# Sheet8.net
KiCad netlist of a schematic drawn in Altium Designer
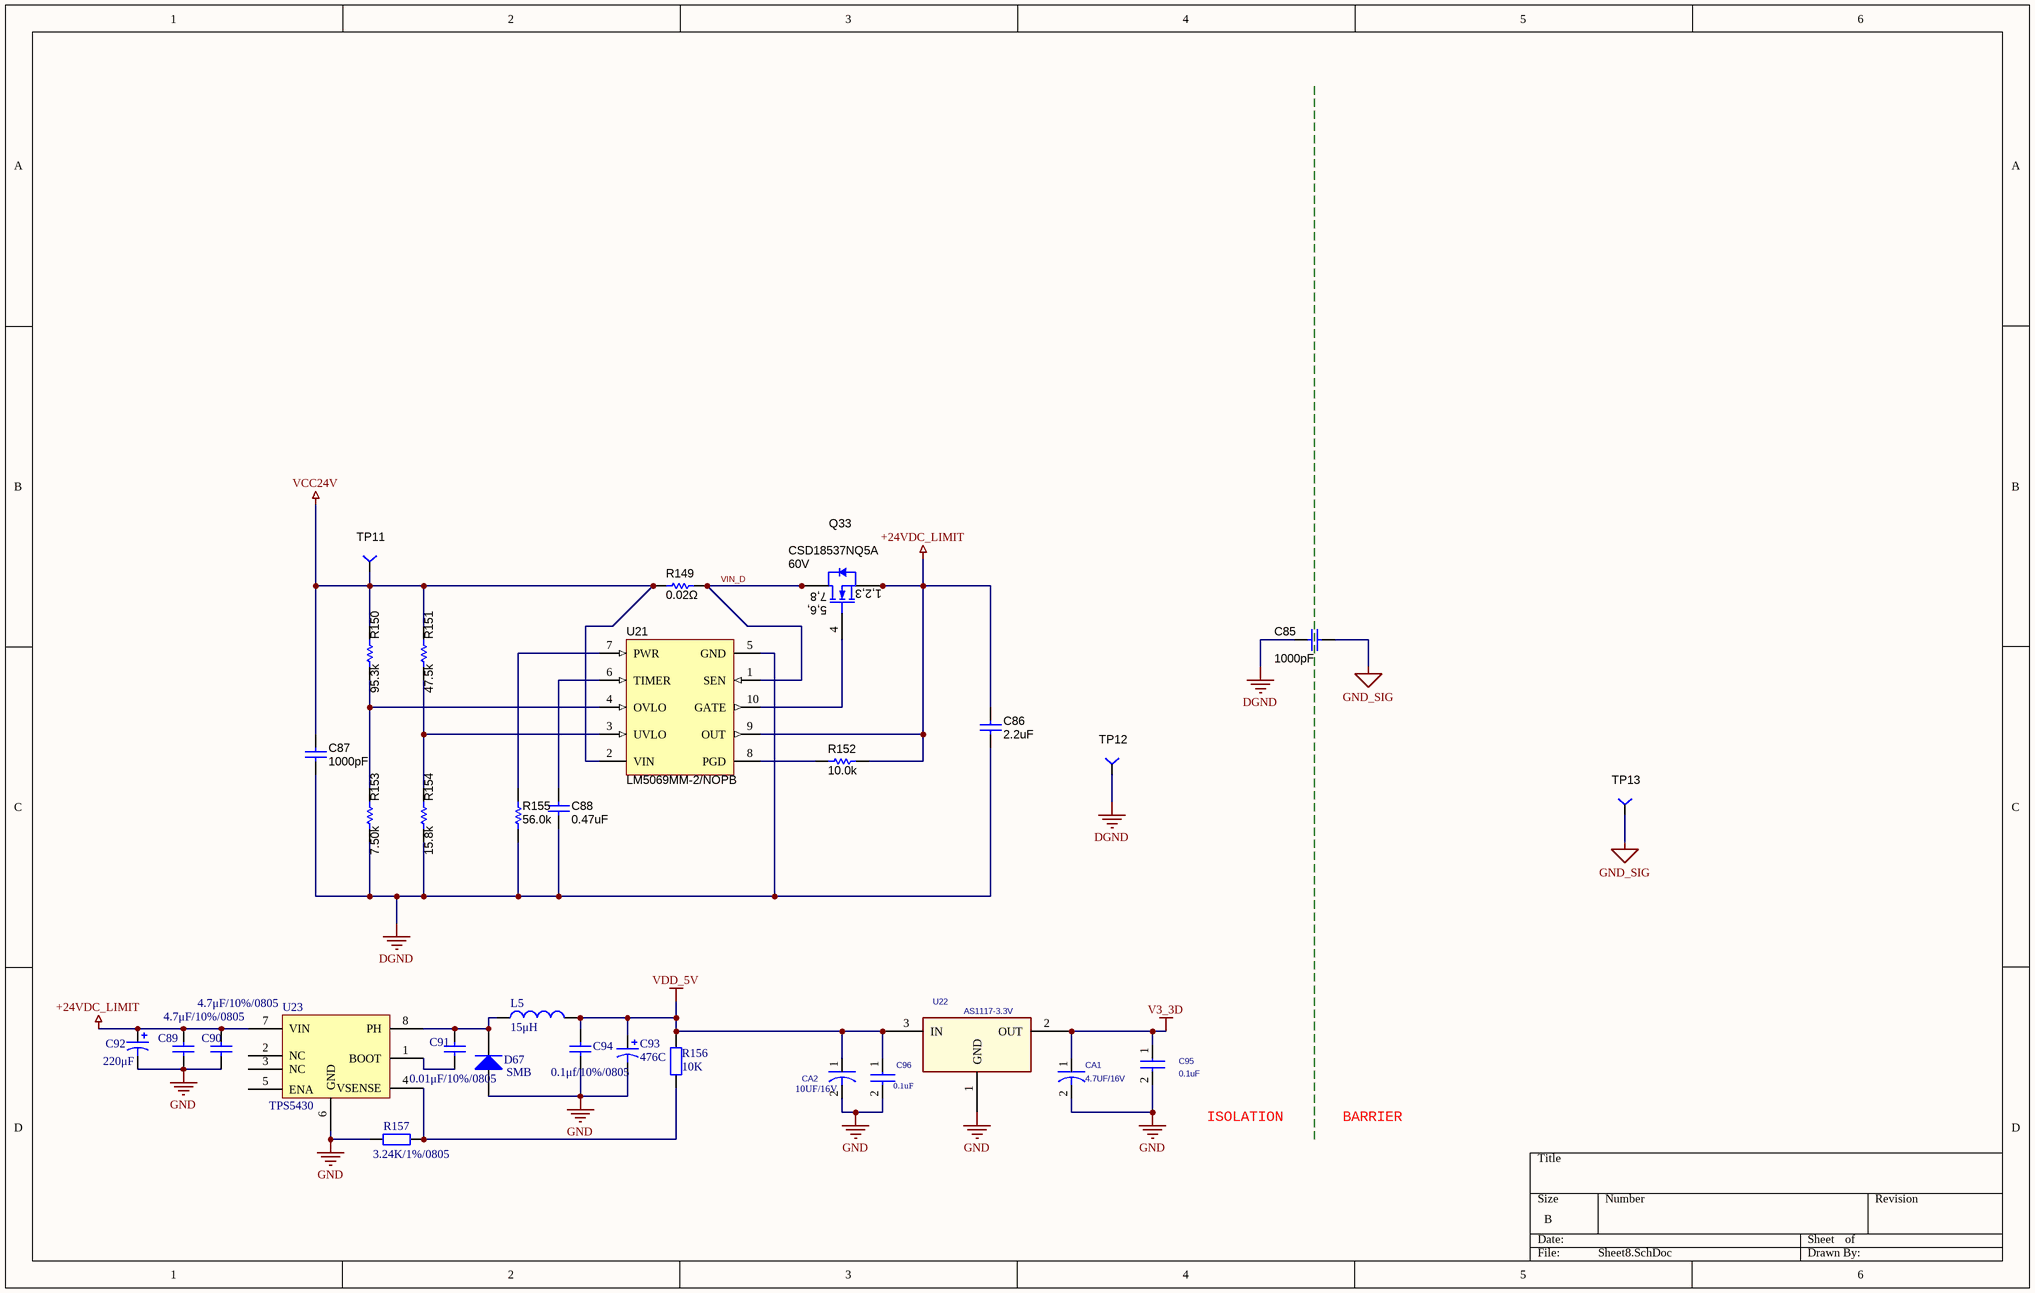
[diagram p0: Sheet8.SchDoc]

(export (version "E")
  (design (tool "Eeschema 10.0.6"))
  (components
    (comp (ref "C85")
      (value "1000pF")
      (footprint "1206")
      (description "CAP, CERM, 1000pF, 2KV 10% X7R 1206")
      (fields
        (field (name "PARTNUMBER") "202R18W102KV4E")
        (field (name "MANUFACTURER") "Johanson Dielectrics Inc")
        (field (name "PUBLISHER") "Texas Instruments")
      )
      (libsource (lib "TI-INDIA-ALTIUM") (part "202R18W102KV4E"))
    )
    (comp (ref "C86")
      (value "GRM32ER72A225KA35L")
      (footprint "1210")
      (description "CAP, CERM, 2.2uF, 100V, +/-10%, X7R, 1210")
      (fields
        (field (name "VALUEDISPLAYED") "2.2uF")
        (field (name "MANUFACTURER") "MuRata")
        (field (name "PUBLISHER") "Texas Instruments")
      )
      (libsource (lib "Capacitor_Ceramic") (part "GRM32ER72A225KA35L"))
    )
    (comp (ref "C87")
      (value "06031C102JAT2A")
      (footprint "0805_cap")
      (description "CAP, CERM, 1000pF, 100V, +/-5%, X7R, 0603")
      (fields
        (field (name "VALUEDISPLAYED") "1000pF")
        (field (name "MANUFACTURER") "AVX")
        (field (name "PUBLISHER") "Texas Instruments")
      )
      (libsource (lib "Capacitor_Ceramic") (part "06031C102JAT2A"))
    )
    (comp (ref "C88")
      (value "UMK107ABJ474KA-T")
      (footprint "0805_cap")
      (description "CAP, CERM, 0.47uF, 50V, 10%, X5R, 0603")
      (fields
        (field (name "MANUFACTURER") "Taiyo Yuden")
        (field (name "VALUEDISPLAYED") "0.47uF")
        (field (name "PUBLISHER") "Texas Instruments")
      )
      (libsource (lib "TI-INDIA-ALTIUM") (part "UMK107ABJ474KA-T"))
    )
    (comp (ref "C89")
      (value "4.7μF/10%/0805")
      (footprint "0805_CAP")
      (description "Capacitor")
      (fields (field (name "PUBLISHER") "Altium Limited"))
      (libsource (lib "Miscellaneous Devices") (part "Cap"))
    )
    (comp (ref "C90")
      (value "4.7μF/10%/0805")
      (footprint "0805_CAP")
      (description "Capacitor")
      (fields (field (name "PUBLISHER") "Altium Limited"))
      (libsource (lib "Miscellaneous Devices") (part "Cap"))
    )
    (comp (ref "C91")
      (value "0.01μF/10%/0805")
      (footprint "0805_CAP")
      (description "Capacitor")
      (fields (field (name "PUBLISHER") "Altium Limited"))
      (libsource (lib "Miscellaneous Devices") (part "Cap"))
    )
    (comp (ref "C92")
      (value "220μF")
      (footprint "CZ3.0/6.5")
      (description "Polarized Capacitor (Radial)")
      (fields (field (name "PUBLISHER") "Altium Limited"))
      (libsource (lib "Miscellaneous Devices") (part "Cap Pol1"))
    )
    (comp (ref "C93")
      (value "476C")
      (footprint "7343-43")
      (description "Polarized Capacitor (Radial)")
      (fields (field (name "PUBLISHER") "Altium Limited"))
      (libsource (lib "Miscellaneous Devices") (part "Cap Pol1"))
    )
    (comp (ref "C94")
      (value "0.1μf/10%/0805")
      (footprint "0805_CAP")
      (description "Capacitor")
      (fields (field (name "PUBLISHER") "Altium Limited"))
      (libsource (lib "Miscellaneous Devices") (part "Cap"))
    )
    (comp (ref "C95") (value "0.1uF") (footprint "0805_CAP") (libsource (lib "v3") (part "C")))
    (comp (ref "C96") (value "0.1uF") (footprint "0805_CAP") (libsource (lib "v3") (part "C")))
    (comp (ref "CA1") (value "4.7UF/16V") (footprint "3528cap") (libsource (lib "v3") (part "ECAP")))
    (comp (ref "CA2") (value "10UF/16V") (footprint "3528cap") (libsource (lib "v3") (part "ECAP")))
    (comp (ref "D67")
      (value "SMB")
      (footprint "SMB")
      (description "3 Amp Medium Power Silicon Rectifier Diode")
      (fields (field (name "PUBLISHER") "Altium Limited"))
      (libsource (lib "Miscellaneous Devices") (part "Diode 1N5408"))
    )
    (comp (ref "L5")
      (value "15μH")
      (footprint "GSDS104C2")
      (description "Inductor")
      (fields (field (name "PUBLISHER") "Altium Limited"))
      (libsource (lib "Miscellaneous Devices") (part "Inductor"))
    )
    (comp (ref "Q33")
      (value "CSD18537NQ5A")
      (footprint "TRANS_NexFET_Q5A")
      (description "MOSFET, N-CH, 60V, 50A, SON 5x6mm")
      (fields
        (field (name "ALTIUM_VALUE") "60V")
        (field (name "MANUFACTURER") "Texas Instruments")
        (field (name "PUBLISHER") "Texas Instruments")
      )
      (libsource (lib "FETs") (part "CSD18537NQ5A"))
    )
    (comp (ref "R149")
      (value "0.02Ω")
      (footprint "1206")
      (description "RES, 0.02 ohm, 1%, 1W, 1206")
      (fields
        (field (name "PARTNUMBER") "PRL1632-R020-F-T1")
        (field (name "MANUFACTURER") "Susumu Co Ltd")
        (field (name "PUBLISHER") "Texas Instruments")
      )
      (libsource (lib "Resistor_1206") (part "PRL1632-R020-F-T1"))
    )
    (comp (ref "R150")
      (value "95.3k")
      (footprint "0805")
      (description "RES, 95.3k ohm, 1%, 0.1W, 0603")
      (fields
        (field (name "PARTNUMBER") "CRCW060395K3FKEA")
        (field (name "MANUFACTURER") "Vishay-Dale")
        (field (name "PUBLISHER") "Texas Instruments")
      )
      (libsource (lib "Resistor_0603") (part "CRCW060395K3FKEA"))
    )
    (comp (ref "R151")
      (value "47.5k")
      (footprint "0805")
      (description "RES, 47.5k ohm, 1%, 0.1W, 0603")
      (fields
        (field (name "PARTNUMBER") "CRCW060347K5FKEA")
        (field (name "MANUFACTURER") "Vishay-Dale")
        (field (name "PUBLISHER") "Texas Instruments")
      )
      (libsource (lib "Resistor_0603") (part "CRCW060347K5FKEA"))
    )
    (comp (ref "R152")
      (value "10.0k")
      (footprint "0805")
      (description "RES, 10.0k ohm, 1%, 0.1W, 0603")
      (fields
        (field (name "PARTNUMBER") "CRCW060310K0FKEA")
        (field (name "MANUFACTURER") "Vishay-Dale")
        (field (name "PUBLISHER") "Texas Instruments")
      )
      (libsource (lib "Resistor_0603") (part "CRCW060310K0FKEA"))
    )
    (comp (ref "R153")
      (value "7.50k")
      (footprint "0805")
      (description "RES, 7.50k ohm, 1%, 0.1W, 0603")
      (fields
        (field (name "PARTNUMBER") "CRCW06037K50FKEA")
        (field (name "MANUFACTURER") "Vishay-Dale")
        (field (name "PUBLISHER") "Texas Instruments")
      )
      (libsource (lib "Resistor_0603") (part "CRCW06037K50FKEA"))
    )
    (comp (ref "R154")
      (value "15.8k")
      (footprint "0805")
      (description "RES, 15.8k ohm, 1%, 0.1W, 0603")
      (fields
        (field (name "PARTNUMBER") "CRCW060315K8FKEA")
        (field (name "MANUFACTURER") "Vishay-Dale")
        (field (name "PUBLISHER") "Texas Instruments")
      )
      (libsource (lib "Resistor_0603") (part "CRCW060315K8FKEA"))
    )
    (comp (ref "R155")
      (value "56.0k")
      (footprint "0805")
      (description "RES, 56.0k ohm, 0.1%, 0.1W, 0603")
      (fields
        (field (name "PARTNUMBER") "RG1608P-563-B-T5")
        (field (name "MANUFACTURER") "Susumu Co Ltd")
        (field (name "PUBLISHER") "Texas Instruments")
      )
      (libsource (lib "Resistor_0603") (part "RG1608P-563-B-T5"))
    )
    (comp (ref "R156")
      (value "10K")
      (footprint "0805")
      (description "Resistor")
      (fields (field (name "PUBLISHER") "Altium Limited"))
      (libsource (lib "") (part "Res2_1"))
    )
    (comp (ref "R157")
      (value "3.24K/1%/0805")
      (footprint "0805")
      (description "Resistor")
      (fields (field (name "PUBLISHER") "Altium Limited"))
      (libsource (lib "Miscellaneous Devices") (part "Res2"))
    )
    (comp (ref "TP11")
      (value "TP-040_RND")
      (footprint "TP-040_RND")
      (description "Test Point, O.040 Hole")
      (fields (field (name "MANUFACTURER") "Standard"))
      (libsource (lib "PADSlegacy_Hardware") (part "TP-040_RND"))
    )
    (comp (ref "TP12")
      (value "TP-040_RND")
      (footprint "TP-040_RND")
      (description "Test Point, O.040 Hole")
      (fields (field (name "MANUFACTURER") "Standard"))
      (libsource (lib "PADSlegacy_Hardware") (part "TP-040_RND"))
    )
    (comp (ref "TP13")
      (value "TP-040_RND")
      (footprint "TP-040_RND")
      (description "Test Point, O.040 Hole")
      (fields (field (name "MANUFACTURER") "Standard"))
      (libsource (lib "PADSlegacy_Hardware") (part "TP-040_RND"))
    )
    (comp (ref "U21")
      (value "LM5069MM-2/NOPB")
      (footprint "MUB10A_N")
      (fields
        (field (name "MANUFACTURER") "National Semiconductor")
        (field (name "PUBLISHER") "Altium Limited")
      )
      (libsource (lib "NSC MiscPower") (part "LM5069MM-2/NOPB"))
    )
    (comp (ref "U22") (value "AS1117-3.3V") (libsource (lib "v3") (part "AS1117")))
    (comp (ref "U23") (value "TPS5430") (footprint "SO-G8") (libsource (lib "SCHLIBRARIES") (part "TPS5430")))
  )
  (nets
    (net (code "1") (name "+24VDC_LIMIT") (class "Default")
      (node (ref "C86") (pin "1") (pinfunction "1_1") (pintype "passive"))
      (node (ref "C89") (pin "2") (pinfunction "2_2") (pintype "passive"))
      (node (ref "C90") (pin "2") (pinfunction "2_2") (pintype "passive"))
      (node (ref "C92") (pin "1") (pinfunction "1_1") (pintype "passive"))
      (node (ref "Q33") (pin "1") (pinfunction "S_1") (pintype "passive"))
      (node (ref "Q33") (pin "2") (pinfunction "S_2") (pintype "passive"))
      (node (ref "Q33") (pin "3") (pinfunction "S_3") (pintype "passive"))
      (node (ref "R152") (pin "1") (pinfunction "1_1") (pintype "passive"))
      (node (ref "U21") (pin "9") (pinfunction "OUT_9") (pintype "output"))
      (node (ref "U23") (pin "7") (pinfunction "VIN_7") (pintype "passive"))
    )
    (net (code "2") (name "/VIN_D") (class "Default")
      (node (ref "Q33") (pin "5") (pinfunction "D_5") (pintype "passive"))
      (node (ref "Q33") (pin "6") (pinfunction "D_6") (pintype "passive"))
      (node (ref "Q33") (pin "7") (pinfunction "D_7") (pintype "passive"))
      (node (ref "Q33") (pin "8") (pinfunction "D_8") (pintype "passive"))
      (node (ref "Q33") (pin "9") (pinfunction "D_9") (pintype "passive"))
      (node (ref "R149") (pin "2") (pinfunction "2_2") (pintype "passive"))
      (node (ref "U21") (pin "1") (pinfunction "SEN_1") (pintype "input"))
    )
    (net (code "3") (name "DGND") (class "Default")
      (node (ref "C85") (pin "1") (pinfunction "1_1") (pintype "passive"))
      (node (ref "C86") (pin "2") (pinfunction "2_2") (pintype "passive"))
      (node (ref "C87") (pin "2") (pinfunction "2_2") (pintype "passive"))
      (node (ref "C88") (pin "2") (pinfunction "2_2") (pintype "passive"))
      (node (ref "R153") (pin "1") (pinfunction "1_1") (pintype "passive"))
      (node (ref "R154") (pin "1") (pinfunction "1_1") (pintype "passive"))
      (node (ref "R155") (pin "1") (pinfunction "1_1") (pintype "passive"))
      (node (ref "TP12") (pin "1") (pinfunction "1_1") (pintype "passive"))
      (node (ref "U21") (pin "5") (pinfunction "GND_5") (pintype "power_in"))
    )
    (net (code "4") (name "GND") (class "Default")
      (node (ref "C89") (pin "1") (pinfunction "1_1") (pintype "passive"))
      (node (ref "C90") (pin "1") (pinfunction "1_1") (pintype "passive"))
      (node (ref "C92") (pin "2") (pinfunction "2_2") (pintype "passive"))
      (node (ref "C93") (pin "2") (pinfunction "2_2") (pintype "passive"))
      (node (ref "C94") (pin "1") (pinfunction "1_1") (pintype "passive"))
      (node (ref "C95") (pin "2") (pinfunction "2_2") (pintype "passive"))
      (node (ref "C96") (pin "2") (pinfunction "2_2") (pintype "passive"))
      (node (ref "CA1") (pin "2") (pinfunction "2_2") (pintype "passive"))
      (node (ref "CA2") (pin "2") (pinfunction "2_2") (pintype "passive"))
      (node (ref "D67") (pin "1") (pinfunction "A_1") (pintype "passive"))
      (node (ref "R157") (pin "2") (pinfunction "2_2") (pintype "passive"))
      (node (ref "U22") (pin "1") (pinfunction "GND_1") (pintype "passive"))
      (node (ref "U23") (pin "6") (pinfunction "GND_6") (pintype "passive"))
    )
    (net (code "5") (name "GND_SIG") (class "Default")
      (node (ref "C85") (pin "2") (pinfunction "2_2") (pintype "passive"))
      (node (ref "TP13") (pin "1") (pinfunction "1_1") (pintype "passive"))
    )
    (net (code "6") (name "Net-(D67-K)") (class "Default")
      (node (ref "C91") (pin "2") (pinfunction "2_2") (pintype "passive"))
      (node (ref "D67") (pin "2") (pinfunction "K_2") (pintype "passive"))
      (node (ref "L5") (pin "1") (pinfunction "1_1") (pintype "passive"))
      (node (ref "U23") (pin "8") (pinfunction "PH_8") (pintype "passive"))
    )
    (net (code "7") (name "Net-(Q33-G)") (class "Default")
      (node (ref "Q33") (pin "4") (pinfunction "G_4") (pintype "passive"))
      (node (ref "U21") (pin "10") (pinfunction "GATE_10") (pintype "output"))
    )
    (net (code "8") (name "Net-(U21-OVLO)") (class "Default")
      (node (ref "R150") (pin "1") (pinfunction "1_1") (pintype "passive"))
      (node (ref "R153") (pin "2") (pinfunction "2_2") (pintype "passive"))
      (node (ref "U21") (pin "4") (pinfunction "OVLO_4") (pintype "input"))
    )
    (net (code "9") (name "Net-(U21-PGD)") (class "Default")
      (node (ref "R152") (pin "2") (pinfunction "2_2") (pintype "passive"))
      (node (ref "U21") (pin "8") (pinfunction "PGD_8") (pintype "open_collector"))
    )
    (net (code "10") (name "Net-(U21-PWR)") (class "Default")
      (node (ref "R155") (pin "2") (pinfunction "2_2") (pintype "passive"))
      (node (ref "U21") (pin "7") (pinfunction "PWR_7") (pintype "input"))
    )
    (net (code "11") (name "Net-(U21-TIMER)") (class "Default")
      (node (ref "C88") (pin "1") (pinfunction "1_1") (pintype "passive"))
      (node (ref "U21") (pin "6") (pinfunction "TIMER_6") (pintype "input"))
    )
    (net (code "12") (name "Net-(U21-UVLO)") (class "Default")
      (node (ref "R151") (pin "1") (pinfunction "1_1") (pintype "passive"))
      (node (ref "R154") (pin "2") (pinfunction "2_2") (pintype "passive"))
      (node (ref "U21") (pin "3") (pinfunction "UVLO_3") (pintype "input"))
    )
    (net (code "13") (name "Net-(U23-BOOT)") (class "Default")
      (node (ref "C91") (pin "1") (pinfunction "1_1") (pintype "passive"))
      (node (ref "U23") (pin "1") (pinfunction "BOOT_1") (pintype "passive"))
    )
    (net (code "14") (name "Net-(U23-VSENSE)") (class "Default")
      (node (ref "R156") (pin "1") (pinfunction "1_1") (pintype "passive"))
      (node (ref "R157") (pin "1") (pinfunction "1_1") (pintype "passive"))
      (node (ref "U23") (pin "4") (pinfunction "VSENSE_4") (pintype "passive"))
    )
    (net (code "15") (name "V3_3D") (class "Default")
      (node (ref "C95") (pin "1") (pinfunction "1_1") (pintype "passive"))
      (node (ref "CA1") (pin "1") (pinfunction "1_1") (pintype "passive"))
      (node (ref "U22") (pin "2") (pinfunction "OUT_2") (pintype "passive"))
    )
    (net (code "16") (name "VCC24V") (class "Default")
      (node (ref "C87") (pin "1") (pinfunction "1_1") (pintype "passive"))
      (node (ref "R149") (pin "1") (pinfunction "1_1") (pintype "passive"))
      (node (ref "R150") (pin "2") (pinfunction "2_2") (pintype "passive"))
      (node (ref "R151") (pin "2") (pinfunction "2_2") (pintype "passive"))
      (node (ref "TP11") (pin "1") (pinfunction "1_1") (pintype "passive"))
      (node (ref "U21") (pin "2") (pinfunction "VIN_2") (pintype "power_in"))
    )
    (net (code "17") (name "VDD_5V") (class "Default")
      (node (ref "C93") (pin "1") (pinfunction "1_1") (pintype "passive"))
      (node (ref "C94") (pin "2") (pinfunction "2_2") (pintype "passive"))
      (node (ref "C96") (pin "1") (pinfunction "1_1") (pintype "passive"))
      (node (ref "CA2") (pin "1") (pinfunction "1_1") (pintype "passive"))
      (node (ref "L5") (pin "2") (pinfunction "2_2") (pintype "passive"))
      (node (ref "R156") (pin "2") (pinfunction "2_2") (pintype "passive"))
      (node (ref "U22") (pin "3") (pinfunction "IN_3") (pintype "passive"))
    )
    (net (code "18") (name "unconnected-(U23-ENA-Pad5)") (class "Default")
      (node (ref "U23") (pin "5") (pinfunction "ENA_5") (pintype "passive"))
    )
    (net (code "19") (name "unconnected-(U23-NC-Pad2)") (class "Default")
      (node (ref "U23") (pin "2") (pinfunction "NC_2") (pintype "passive"))
    )
    (net (code "20") (name "unconnected-(U23-NC-Pad3)") (class "Default")
      (node (ref "U23") (pin "3") (pinfunction "NC_3") (pintype "passive"))
    )
  )
)
